# US.net
KiCad netlist of a schematic drawn in EAGLE
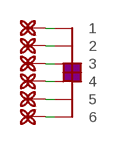
[diagram p0: schematic, sheet 1]

(export (version "E")
  (design (tool "Eeschema 10.0.6"))
  (components
    (comp (ref "C1")
      (value "6P6C_FEMALESMD")
      (footprint "eagle-import:6P6C_FEMALE")
      (libsource (lib "eagle-import") (part "6P6C_FEMALESMD"))
    )
    (comp (ref "PAD1")
      (value "BETTERPAD_2.54")
      (footprint "eagle-import:SUPERIORSIM")
      (libsource (lib "eagle-import") (part "BETTERPAD_2.54"))
    )
    (comp (ref "PAD2")
      (value "BETTERPAD_2.54")
      (footprint "eagle-import:SUPERIORSIM")
      (libsource (lib "eagle-import") (part "BETTERPAD_2.54"))
    )
    (comp (ref "PAD3")
      (value "BETTERPAD_2.54")
      (footprint "eagle-import:SUPERIORSIM")
      (libsource (lib "eagle-import") (part "BETTERPAD_2.54"))
    )
    (comp (ref "PAD4")
      (value "BETTERPAD_2.54")
      (footprint "eagle-import:SUPERIORSIM")
      (libsource (lib "eagle-import") (part "BETTERPAD_2.54"))
    )
    (comp (ref "PAD5")
      (value "BETTERPAD_2.54")
      (footprint "eagle-import:SUPERIORSIM")
      (libsource (lib "eagle-import") (part "BETTERPAD_2.54"))
    )
    (comp (ref "PAD6")
      (value "BETTERPAD_2.54")
      (footprint "eagle-import:SUPERIORSIM")
      (libsource (lib "eagle-import") (part "BETTERPAD_2.54"))
    )
  )
  (nets
    (net (code "1") (name "Net-(PAD1-P)") (class "Default")
      (node (ref "C1") (pin "1") (pinfunction "1_1") (pintype "bidirectional"))
      (node (ref "PAD1") (pin ".") (pinfunction "P_.") (pintype "passive"))
    )
    (net (code "2") (name "Net-(PAD2-P)") (class "Default")
      (node (ref "C1") (pin "2") (pinfunction "2_2") (pintype "bidirectional"))
      (node (ref "PAD2") (pin ".") (pinfunction "P_.") (pintype "passive"))
    )
    (net (code "3") (name "Net-(PAD3-P)") (class "Default")
      (node (ref "C1") (pin "3") (pinfunction "3_3") (pintype "bidirectional"))
      (node (ref "PAD3") (pin ".") (pinfunction "P_.") (pintype "passive"))
    )
    (net (code "4") (name "Net-(PAD4-P)") (class "Default")
      (node (ref "C1") (pin "4") (pinfunction "4_4") (pintype "bidirectional"))
      (node (ref "PAD4") (pin ".") (pinfunction "P_.") (pintype "passive"))
    )
    (net (code "5") (name "Net-(PAD5-P)") (class "Default")
      (node (ref "C1") (pin "5") (pinfunction "5_5") (pintype "bidirectional"))
      (node (ref "PAD5") (pin ".") (pinfunction "P_.") (pintype "passive"))
    )
    (net (code "6") (name "Net-(PAD6-P)") (class "Default")
      (node (ref "C1") (pin "6") (pinfunction "6_6") (pintype "bidirectional"))
      (node (ref "PAD6") (pin ".") (pinfunction "P_.") (pintype "passive"))
    )
  )
)
